# MD070B_CONTROL.net
KiCad netlist of a schematic drawn in Altium Designer
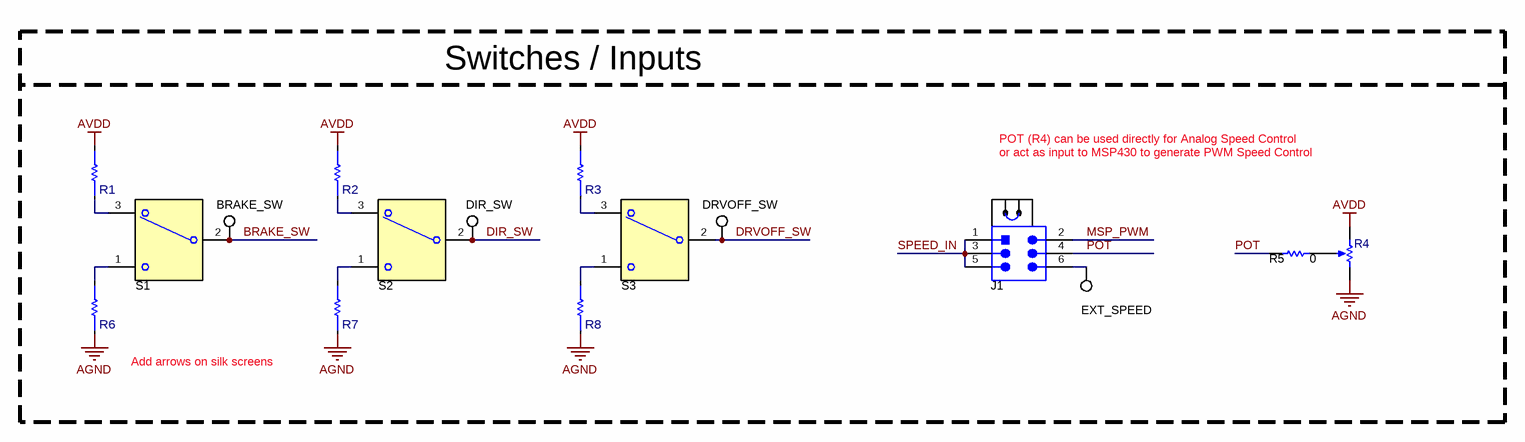
[diagram p0: MD070B_CONTROL.SchDoc]

(export (version "E")
  (design (tool "Eeschema 10.0.6"))
  (components
    (comp (ref "J1")
      (value "Header_3x2")
      (footprint "TSW-103-07-G-D")
      (description "Header, 100mil, 3x2, Gold, TH")
      (fields (field (name "PARTNUMBER") "TSW-103-07-G-D") (field (name "MANUFACTURER") "Samtec"))
      (libsource (lib "Altium Vault - TI") (part "Header_3x2"))
    )
    (comp (ref "R1")
      (value "ERA-3ARB103V")
      (footprint "FP-ERA-3ARB103V_0603-MFG")
      (description "Res Thin Film 0603 10K Ohm 0.1% 1/10W ±10ppm/°C Molded SMD SMD Punched Carrier T/R")
      (fields (field (name "MANUFACTURER") "Panasonic") (field (name "DIGIKEY PART NUMBER") "P10KBDCT-ND"))
      (libsource (lib "Altium Vault - TI") (part "SYM-ERA-3ARB103V"))
    )
    (comp (ref "R2")
      (value "ERA-3ARB103V")
      (footprint "FP-ERA-3ARB103V_0603-MFG")
      (description "Res Thin Film 0603 10K Ohm 0.1% 1/10W ±10ppm/°C Molded SMD SMD Punched Carrier T/R")
      (fields (field (name "MANUFACTURER") "Panasonic") (field (name "DIGIKEY PART NUMBER") "P10KBDCT-ND"))
      (libsource (lib "Altium Vault - TI") (part "SYM-ERA-3ARB103V"))
    )
    (comp (ref "R3")
      (value "ERA-3ARB103V")
      (footprint "FP-ERA-3ARB103V_0603-MFG")
      (description "Res Thin Film 0603 10K Ohm 0.1% 1/10W ±10ppm/°C Molded SMD SMD Punched Carrier T/R")
      (fields (field (name "MANUFACTURER") "Panasonic") (field (name "DIGIKEY PART NUMBER") "P10KBDCT-ND"))
      (libsource (lib "Altium Vault - TI") (part "SYM-ERA-3ARB103V"))
    )
    (comp (ref "R4")
      (value "3352T-1-253LF")
      (footprint "Bourns_3352T")
      (description "Trimmer Potentiometer, 25kohm, 0.5W, TH")
      (fields (field (name "MANUFACTURER") "Bourns") (field (name "PUBLISHER") "Texas Instruments"))
      (libsource (lib "Altium Vault - TI") (part "Potentiometer"))
    )
    (comp (ref "R5")
      (value "ERJ-3GEY0R00V")
      (footprint "0603L")
      (description "RES, 0, 5%, 0.1 W, AEC-Q200 Grade 0, 0603")
      (fields (field (name "MANUFACTURER") "Panasonic") (field (name "VALUEDISPLAYED") "0"))
      (libsource (lib "Altium Vault - TI") (part "Resistor"))
    )
    (comp (ref "R6")
      (value "ERA-3ARB103V")
      (footprint "FP-ERA-3ARB103V_0603-MFG")
      (description "Res Thin Film 0603 10K Ohm 0.1% 1/10W ±10ppm/°C Molded SMD SMD Punched Carrier T/R")
      (fields (field (name "MANUFACTURER") "Panasonic") (field (name "DIGIKEY PART NUMBER") "P10KBDCT-ND"))
      (libsource (lib "Altium Vault - TI") (part "SYM-ERA-3ARB103V"))
    )
    (comp (ref "R7")
      (value "ERA-3ARB103V")
      (footprint "FP-ERA-3ARB103V_0603-MFG")
      (description "Res Thin Film 0603 10K Ohm 0.1% 1/10W ±10ppm/°C Molded SMD SMD Punched Carrier T/R")
      (fields (field (name "MANUFACTURER") "Panasonic") (field (name "DIGIKEY PART NUMBER") "P10KBDCT-ND"))
      (libsource (lib "Altium Vault - TI") (part "SYM-ERA-3ARB103V"))
    )
    (comp (ref "R8")
      (value "ERA-3ARB103V")
      (footprint "FP-ERA-3ARB103V_0603-MFG")
      (description "Res Thin Film 0603 10K Ohm 0.1% 1/10W ±10ppm/°C Molded SMD SMD Punched Carrier T/R")
      (fields (field (name "MANUFACTURER") "Panasonic") (field (name "DIGIKEY PART NUMBER") "P10KBDCT-ND"))
      (libsource (lib "Altium Vault - TI") (part "SYM-ERA-3ARB103V"))
    )
    (comp (ref "S1")
      (value "SW_SPDT_COM2_1_3")
      (footprint "SW_B12AP")
      (description "SWITCH TOGGLE SPDT 0.4VA 28V")
      (fields
        (field (name "PARTNUMBER") "B12AP")
        (field (name "MANUFACTURER") "NKK Switches")
        (field (name "PUBLISHER") "Texas Instruments")
      )
      (libsource (lib "Altium Vault - TI") (part "CMP-0002155-2"))
    )
    (comp (ref "S2")
      (value "SW_SPDT_COM2_1_3")
      (footprint "SW_B12AP")
      (description "SWITCH TOGGLE SPDT 0.4VA 28V")
      (fields
        (field (name "PARTNUMBER") "B12AP")
        (field (name "MANUFACTURER") "NKK Switches")
        (field (name "PUBLISHER") "Texas Instruments")
      )
      (libsource (lib "Altium Vault - TI") (part "CMP-0002155-2"))
    )
    (comp (ref "S3")
      (value "SW_SPDT_COM2_1_3")
      (footprint "SW_B12AP")
      (description "SWITCH TOGGLE SPDT 0.4VA 28V")
      (fields
        (field (name "PARTNUMBER") "B12AP")
        (field (name "MANUFACTURER") "NKK Switches")
        (field (name "PUBLISHER") "Texas Instruments")
      )
      (libsource (lib "Altium Vault - TI") (part "CMP-0002155-2"))
    )
    (comp (ref "SH-J1")
      (value "SNT-100-BK-G")
      (footprint "SNT-100-BK-G")
      (description "Shunt, 100mil, Gold plated, Black")
      (fields (field (name "ALTERNATE PARTNUMBER") "969102-0000-DA") (field (name "MANUFACTURER") "Samtec"))
      (libsource (lib "Altium Vault - TI") (part "Shunt"))
    )
    (comp (ref "TP1")
      (value "EXT_SPEED")
      (footprint "Keystone5002")
      (description "Test Point, Miniature, White, TH")
      (fields
        (field (name "MANUFACTURER") "Keystone")
        (field (name "PARTNUMBER") "5002")
        (field (name "PUBLISHER") "Texas Instruments")
      )
      (libsource (lib "Altium Vault - TI") (part "5002"))
    )
    (comp (ref "TP2")
      (value "BRAKE_SW")
      (footprint "Keystone5002")
      (description "Test Point, Miniature, White, TH")
      (fields
        (field (name "MANUFACTURER") "Keystone")
        (field (name "PARTNUMBER") "5002")
        (field (name "PUBLISHER") "Texas Instruments")
      )
      (libsource (lib "Altium Vault - TI") (part "5002"))
    )
    (comp (ref "TP3")
      (value "DIR_SW")
      (footprint "Keystone5002")
      (description "Test Point, Miniature, White, TH")
      (fields
        (field (name "MANUFACTURER") "Keystone")
        (field (name "PARTNUMBER") "5002")
        (field (name "PUBLISHER") "Texas Instruments")
      )
      (libsource (lib "Altium Vault - TI") (part "5002"))
    )
    (comp (ref "TP4")
      (value "DRVOFF_SW")
      (footprint "Keystone5002")
      (description "Test Point, Miniature, White, TH")
      (fields
        (field (name "MANUFACTURER") "Keystone")
        (field (name "PARTNUMBER") "5002")
        (field (name "PUBLISHER") "Texas Instruments")
      )
      (libsource (lib "Altium Vault - TI") (part "5002"))
    )
  )
  (nets
    (net (code "1") (name "/BRAKE_SW") (class "Default")
      (node (ref "S1") (pin "2") (pinfunction "COM_2") (pintype "passive"))
      (node (ref "TP2") (pin "1") (pintype "passive"))
    )
    (net (code "2") (name "/DIR_SW") (class "Default")
      (node (ref "S2") (pin "2") (pinfunction "COM_2") (pintype "passive"))
      (node (ref "TP3") (pin "1") (pintype "passive"))
    )
    (net (code "3") (name "/DRVOFF_SW") (class "Default")
      (node (ref "S3") (pin "2") (pinfunction "COM_2") (pintype "passive"))
      (node (ref "TP4") (pin "1") (pintype "passive"))
    )
    (net (code "4") (name "/MSP_PWM") (class "Default")
      (node (ref "J1") (pin "2") (pinfunction "2_2") (pintype "passive"))
    )
    (net (code "5") (name "/POT") (class "Default")
      (node (ref "J1") (pin "4") (pinfunction "4_4") (pintype "passive"))
      (node (ref "R5") (pin "1") (pinfunction "1_1") (pintype "passive"))
    )
    (net (code "6") (name "/SPEED_IN") (class "Default")
      (node (ref "J1") (pin "1") (pinfunction "1_1") (pintype "passive"))
      (node (ref "J1") (pin "3") (pinfunction "3_3") (pintype "passive"))
      (node (ref "J1") (pin "5") (pinfunction "5_5") (pintype "passive"))
    )
    (net (code "7") (name "AGND") (class "Default")
      (node (ref "R4") (pin "3") (pinfunction "CW_3") (pintype "passive"))
      (node (ref "R6") (pin "1") (pinfunction "1_1") (pintype "passive"))
      (node (ref "R7") (pin "1") (pinfunction "1_1") (pintype "passive"))
      (node (ref "R8") (pin "1") (pinfunction "1_1") (pintype "passive"))
    )
    (net (code "8") (name "AVDD") (class "Default")
      (node (ref "R1") (pin "2") (pinfunction "2_2") (pintype "passive"))
      (node (ref "R2") (pin "2") (pinfunction "2_2") (pintype "passive"))
      (node (ref "R3") (pin "2") (pinfunction "2_2") (pintype "passive"))
      (node (ref "R4") (pin "1") (pinfunction "CCW_1") (pintype "passive"))
    )
    (net (code "9") (name "Net-(J1-Pad6)") (class "Default")
      (node (ref "J1") (pin "6") (pinfunction "6_6") (pintype "passive"))
      (node (ref "TP1") (pin "1") (pintype "passive"))
    )
    (net (code "10") (name "Net-(R1-Pad1)") (class "Default")
      (node (ref "R1") (pin "1") (pinfunction "1_1") (pintype "passive"))
      (node (ref "S1") (pin "3") (pintype "passive"))
    )
    (net (code "11") (name "Net-(R2-Pad1)") (class "Default")
      (node (ref "R2") (pin "1") (pinfunction "1_1") (pintype "passive"))
      (node (ref "S2") (pin "3") (pintype "passive"))
    )
    (net (code "12") (name "Net-(R3-Pad1)") (class "Default")
      (node (ref "R3") (pin "1") (pinfunction "1_1") (pintype "passive"))
      (node (ref "S3") (pin "3") (pintype "passive"))
    )
    (net (code "13") (name "Net-(R4-WIPER)") (class "Default")
      (node (ref "R4") (pin "2") (pinfunction "WIPER_2") (pintype "passive"))
      (node (ref "R5") (pin "2") (pinfunction "2_2") (pintype "passive"))
    )
    (net (code "14") (name "Net-(R6-Pad2)") (class "Default")
      (node (ref "R6") (pin "2") (pinfunction "2_2") (pintype "passive"))
      (node (ref "S1") (pin "1") (pintype "passive"))
    )
    (net (code "15") (name "Net-(R7-Pad2)") (class "Default")
      (node (ref "R7") (pin "2") (pinfunction "2_2") (pintype "passive"))
      (node (ref "S2") (pin "1") (pintype "passive"))
    )
    (net (code "16") (name "Net-(R8-Pad2)") (class "Default")
      (node (ref "R8") (pin "2") (pinfunction "2_2") (pintype "passive"))
      (node (ref "S3") (pin "1") (pintype "passive"))
    )
  )
)
